# LC_LPF15.net
KiCad netlist of a schematic drawn in Altium Designer
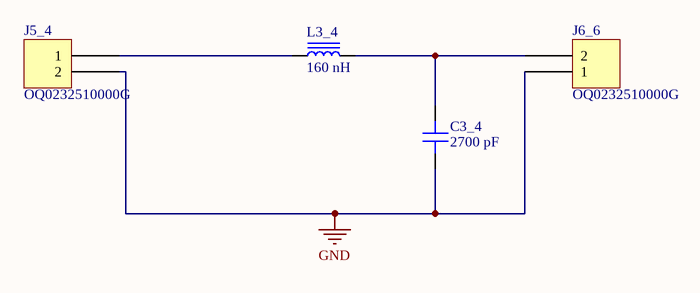
[diagram p0: LC_LPF15.SchDoc]

(export (version "E")
  (design (tool "Eeschema 10.0.6"))
  (components
    (comp (ref "C3_4")
      (value "2700 pF")
      (footprint "CAP 0603_1608")
      (description "CAP CER 2700PF 25V NP0 0603")
      (fields (field (name "PART NUMBER") "C0603C272F3GAC7867") (field (name "MANUFACTURER") "KEMET"))
      (libsource (lib "Celestial Altium Library - altium_library") (part "Capacitor"))
    )
    (comp (ref "J5_4")
      (value "OQ0232510000G")
      (footprint "FCI 06-381-2PIN")
      (description "TERM BLOCK HDR 2POS 90DEG 3.81MM")
      (fields (field (name "MANUFACTURER") "Amphenol Anytek"))
      (libsource (lib "") (part "2 Pin_1"))
    )
    (comp (ref "J6_6")
      (value "OQ0232510000G")
      (footprint "FCI 06-381-2PIN")
      (description "TERM BLOCK HDR 2POS 90DEG 3.81MM")
      (fields (field (name "MANUFACTURER") "Amphenol Anytek"))
      (libsource (lib "Celestial Altium Library - altium_library") (part "2 Pin"))
    )
    (comp (ref "L3_4")
      (value "160 nH")
      (footprint "IND 0402_1005 RF WW")
      (description "FIXED IND 160NH 480MA 330MOHM SM")
      (fields
        (field (name "PART NUMBER") "LQW15CNR16J00D")
        (field (name "MANUFACTURER") "Murata Electronics")
      )
      (libsource (lib "Celestial Altium Library - altium_library") (part "Inductor"))
    )
  )
  (nets
    (net (code "1") (name "GND") (class "Default")
      (node (ref "C3_4") (pin "1") (pinfunction "1_1") (pintype "passive"))
      (node (ref "J5_4") (pin "2") (pinfunction "2_2") (pintype "passive"))
      (node (ref "J6_6") (pin "1") (pinfunction "1_1") (pintype "passive"))
    )
    (net (code "2") (name "Net-(C3_4-Pad2)") (class "Default")
      (node (ref "C3_4") (pin "2") (pinfunction "2_2") (pintype "passive"))
      (node (ref "J6_6") (pin "2") (pinfunction "2_2") (pintype "passive"))
      (node (ref "L3_4") (pin "2") (pinfunction "2_2") (pintype "passive"))
    )
    (net (code "3") (name "Net-(J5_4-Pad1)") (class "Default")
      (node (ref "J5_4") (pin "1") (pinfunction "1_1") (pintype "passive"))
      (node (ref "L3_4") (pin "1") (pinfunction "1_1") (pintype "passive"))
    )
  )
)
